# Control_Panel_PCB.net
KiCad netlist of a schematic drawn in EasyEDA Pro
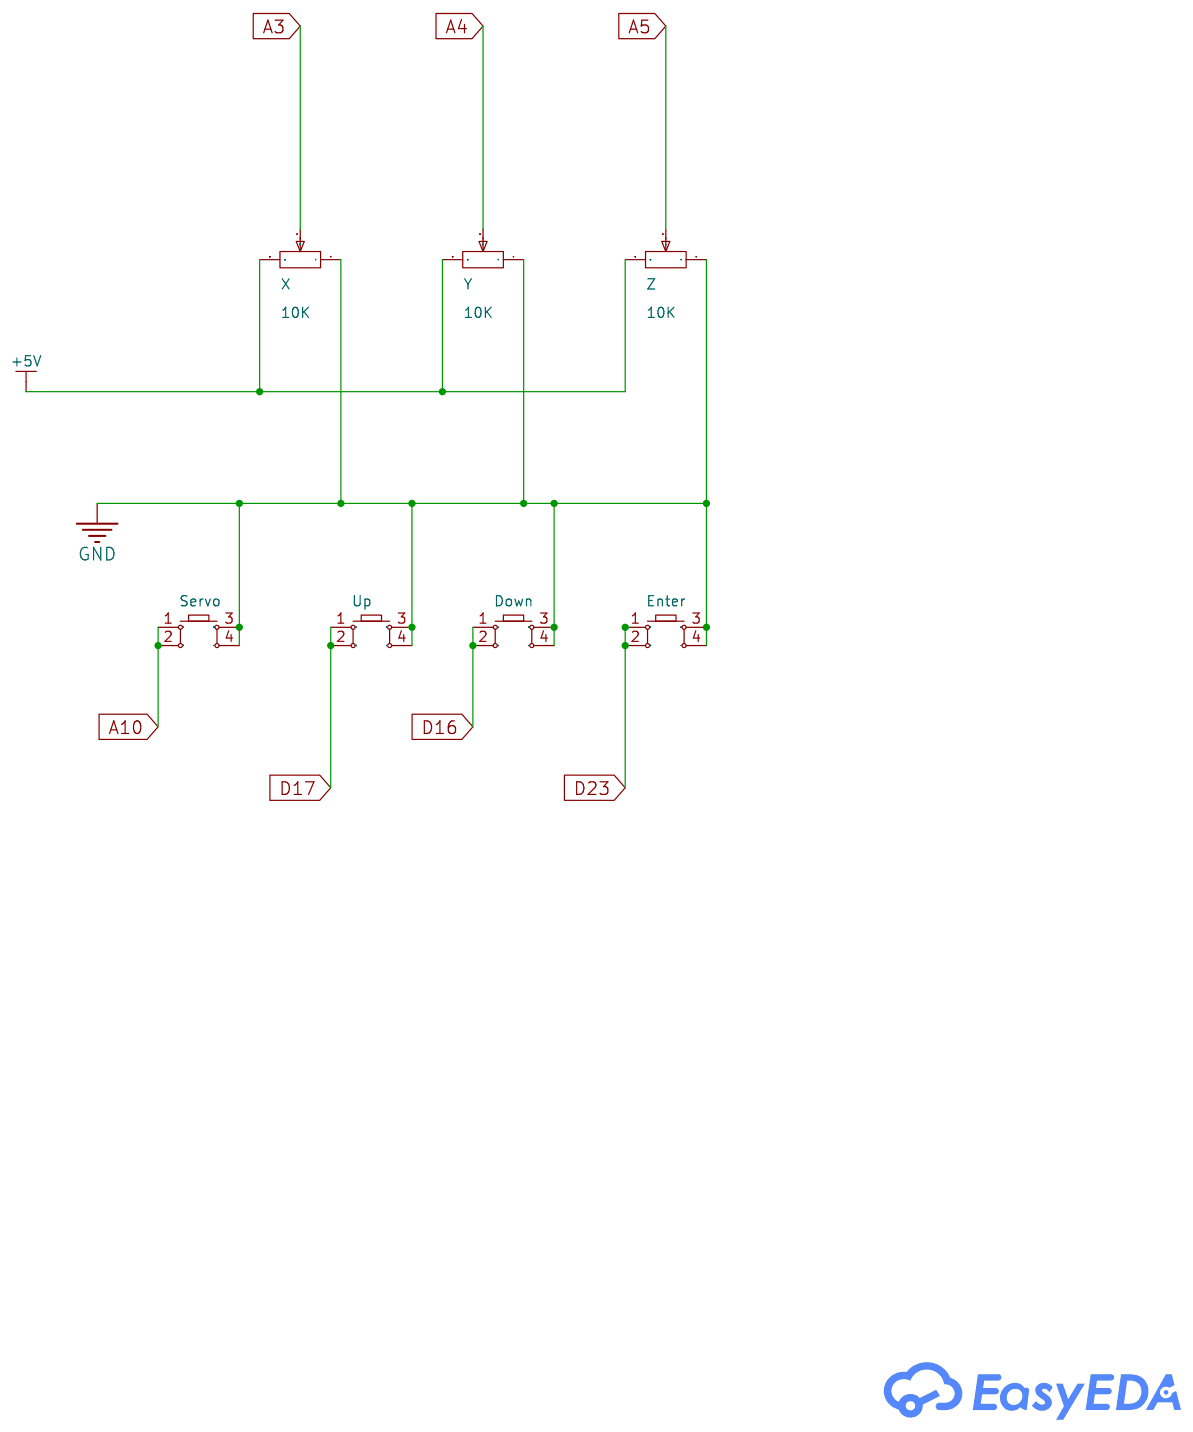
[diagram p0: schematic sheet]

(export (version "E")
  (design (tool "Eeschema 10.0.6"))
  (components
    (comp (ref "Down")
      (value "~")
      (footprint "easyedapro:SW-SMD_4P-L6.0-W6.0-P4.50-LS9.0-2")
      (libsource (lib "easyedapro") (part "轻触按键"))
    )
    (comp (ref "Enter")
      (value "~")
      (footprint "easyedapro:SW-SMD_4P-L6.0-W6.0-P4.50-LS9.0-2")
      (libsource (lib "easyedapro") (part "轻触按键"))
    )
    (comp (ref "Servo")
      (value "~")
      (footprint "easyedapro:SW-SMD_4P-L6.0-W6.0-P4.50-LS9.0-2")
      (libsource (lib "easyedapro") (part "轻触按键"))
    )
    (comp (ref "Up")
      (value "~")
      (footprint "easyedapro:SW-SMD_4P-L6.0-W6.0-P4.50-LS9.0-2")
      (libsource (lib "easyedapro") (part "轻触按键"))
    )
    (comp (ref "X")
      (value "10K")
      (footprint "easyedapro:RES-ADJ-TH_3P-L9.5-W9.5-P2.54-BR-BS")
      (libsource (lib "easyedapro") (part "3386P-1-103LF"))
    )
    (comp (ref "Y")
      (value "10K")
      (footprint "easyedapro:RES-ADJ-TH_3P-L9.5-W9.5-P2.54-BR-BS")
      (libsource (lib "easyedapro") (part "3386P-1-103LF"))
    )
    (comp (ref "Z")
      (value "10K")
      (footprint "easyedapro:RES-ADJ-TH_3P-L9.5-W9.5-P2.54-BR-BS")
      (libsource (lib "easyedapro") (part "3386P-1-103LF"))
    )
  )
  (nets
    (net (code "1") (name "+5V") (class "Default")
      (node (ref "X") (pin "3") (pinfunction "3_3") (pintype "input"))
      (node (ref "Y") (pin "3") (pinfunction "3_3") (pintype "input"))
      (node (ref "Z") (pin "3") (pinfunction "3_3") (pintype "input"))
    )
    (net (code "2") (name "A3") (class "Default")
      (node (ref "X") (pin "2") (pinfunction "2_2") (pintype "input"))
    )
    (net (code "3") (name "A4") (class "Default")
      (node (ref "Y") (pin "2") (pinfunction "2_2") (pintype "input"))
    )
    (net (code "4") (name "A5") (class "Default")
      (node (ref "Z") (pin "2") (pinfunction "2_2") (pintype "input"))
    )
    (net (code "5") (name "A10") (class "Default")
      (node (ref "Servo") (pin "1") (pinfunction "1_1") (pintype "input"))
      (node (ref "Servo") (pin "2") (pinfunction "2_2") (pintype "input"))
    )
    (net (code "6") (name "D16") (class "Default")
      (node (ref "Down") (pin "1") (pinfunction "1_1") (pintype "input"))
      (node (ref "Down") (pin "2") (pinfunction "2_2") (pintype "input"))
    )
    (net (code "7") (name "D17") (class "Default")
      (node (ref "Up") (pin "1") (pinfunction "1_1") (pintype "input"))
      (node (ref "Up") (pin "2") (pinfunction "2_2") (pintype "input"))
    )
    (net (code "8") (name "D23") (class "Default")
      (node (ref "Enter") (pin "1") (pinfunction "1_1") (pintype "input"))
      (node (ref "Enter") (pin "2") (pinfunction "2_2") (pintype "input"))
    )
    (net (code "9") (name "GND") (class "Default")
      (node (ref "Down") (pin "3") (pinfunction "3_3") (pintype "input"))
      (node (ref "Down") (pin "4") (pinfunction "4_4") (pintype "input"))
      (node (ref "Enter") (pin "3") (pinfunction "3_3") (pintype "input"))
      (node (ref "Enter") (pin "4") (pinfunction "4_4") (pintype "input"))
      (node (ref "Servo") (pin "3") (pinfunction "3_3") (pintype "input"))
      (node (ref "Servo") (pin "4") (pinfunction "4_4") (pintype "input"))
      (node (ref "Up") (pin "3") (pinfunction "3_3") (pintype "input"))
      (node (ref "Up") (pin "4") (pinfunction "4_4") (pintype "input"))
      (node (ref "X") (pin "1") (pinfunction "1_1") (pintype "input"))
      (node (ref "Y") (pin "1") (pinfunction "1_1") (pintype "input"))
      (node (ref "Z") (pin "1") (pinfunction "1_1") (pintype "input"))
    )
  )
)
